# single_psg.net
KiCad netlist of a schematic drawn in EAGLE
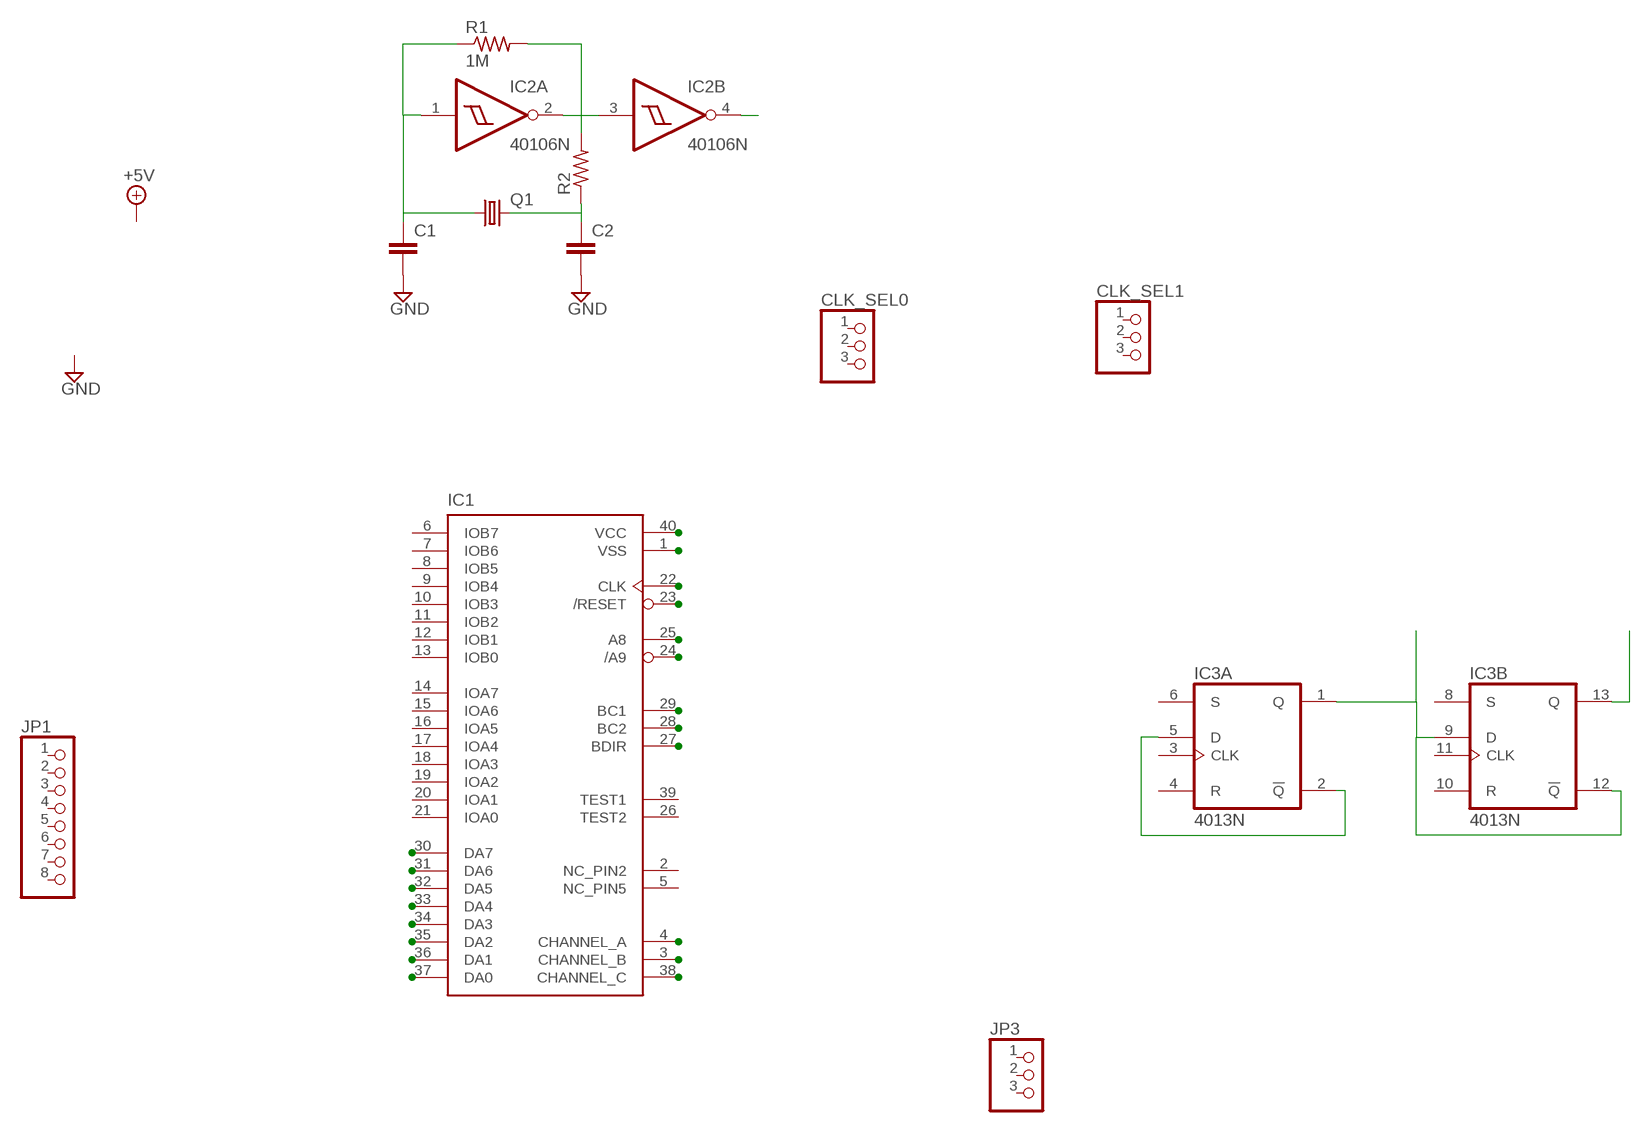
[diagram p0: schematic, sheet 1]

(export (version "E")
  (design (tool "Eeschema 10.0.6"))
  (components
    (comp (ref "C1")
      (value "050X030_0252")
      (footprint "eagle-import:050X030_025_2")
      (libsource (lib "eagle-import") (part "050X030_0252"))
    )
    (comp (ref "C2")
      (value "050X030_0252")
      (footprint "eagle-import:050X030_025_2")
      (libsource (lib "eagle-import") (part "050X030_0252"))
    )
    (comp (ref "CLK_SEL0")
      (value "PINHD-1X3")
      (footprint "eagle-import:1X03")
      (libsource (lib "eagle-import") (part "PINHD-1X3"))
    )
    (comp (ref "CLK_SEL1")
      (value "PINHD-1X3")
      (footprint "eagle-import:1X03")
      (libsource (lib "eagle-import") (part "PINHD-1X3"))
    )
    (comp (ref "IC1")
      (value "AY-3-8910")
      (footprint "eagle-import:DIL40")
      (libsource (lib "eagle-import") (part "AY-3-8910"))
    )
    (comp (ref "IC2")
      (value "40106N")
      (footprint "eagle-import:DIL14")
      (libsource (lib "eagle-import") (part "40106N"))
    )
    (comp (ref "IC3")
      (value "4013N")
      (footprint "eagle-import:DIL14")
      (libsource (lib "eagle-import") (part "4013N"))
    )
    (comp (ref "JP1")
      (value "PINHD-1X8")
      (footprint "eagle-import:1X08")
      (libsource (lib "eagle-import") (part "PINHD-1X8"))
    )
    (comp (ref "JP3")
      (value "PINHD-1X3")
      (footprint "eagle-import:1X03")
      (libsource (lib "eagle-import") (part "PINHD-1X3"))
    )
    (comp (ref "Q1")
      (value "CRYSTALHC18U-V")
      (footprint "eagle-import:HC18U-V")
      (libsource (lib "eagle-import") (part "CRYSTALHC18U-V"))
    )
    (comp (ref "R1")
      (value "1M")
      (footprint "eagle-import:R0207_3")
      (libsource (lib "eagle-import") (part "6MM.3"))
    )
    (comp (ref "R2")
      (value "6MM.3")
      (footprint "eagle-import:R0207_3")
      (libsource (lib "eagle-import") (part "6MM.3"))
    )
  )
  (nets
    (net (code "2") (name "/VCC") (class "Default")
      (node (ref "IC1") (pin "40") (pinfunction "VCC_40") (pintype "power_in"))
    )
    (net (code "3") (name "/VSS") (class "Default")
      (node (ref "IC1") (pin "1") (pinfunction "VSS_1") (pintype "power_in"))
    )
    (net (code "4") (name "GND") (class "Default")
      (node (ref "C1") (pin "2") (pinfunction "2_2") (pintype "passive"))
      (node (ref "C2") (pin "2") (pinfunction "2_2") (pintype "passive"))
    )
    (net (code "5") (name "Net-(C2-Pad1)") (class "Default")
      (node (ref "C2") (pin "1") (pinfunction "1_1") (pintype "passive"))
      (node (ref "Q1") (pin "2") (pinfunction "2_2") (pintype "passive"))
      (node (ref "R2") (pin "1") (pinfunction "1_1") (pintype "passive"))
    )
    (net (code "6") (name "Net-(IC2A-I)") (class "Default")
      (node (ref "C1") (pin "1") (pinfunction "1_1") (pintype "passive"))
      (node (ref "IC2") (pin "1") (pinfunction "I_1") (pintype "input"))
      (node (ref "Q1") (pin "1") (pinfunction "1_1") (pintype "passive"))
      (node (ref "R1") (pin "1") (pinfunction "1_1") (pintype "passive"))
    )
    (net (code "7") (name "Net-(IC2A-O)") (class "Default")
      (node (ref "IC2") (pin "2") (pinfunction "O_2") (pintype "output"))
      (node (ref "IC2") (pin "3") (pinfunction "I_3") (pintype "input"))
      (node (ref "R1") (pin "2") (pinfunction "2_2") (pintype "passive"))
      (node (ref "R2") (pin "2") (pinfunction "2_2") (pintype "passive"))
    )
    (net (code "8") (name "Net-(IC3A-D)") (class "Default")
      (node (ref "IC3") (pin "2") (pinfunction "~{Q}_2") (pintype "output"))
      (node (ref "IC3") (pin "5") (pinfunction "D_5") (pintype "input"))
    )
    (net (code "9") (name "Net-(IC3A-Q)") (class "Default")
      (node (ref "IC3") (pin "1") (pinfunction "Q_1") (pintype "output"))
      (node (ref "IC3") (pin "12") (pinfunction "~{Q}_12") (pintype "output"))
      (node (ref "IC3") (pin "9") (pinfunction "D_9") (pintype "input"))
    )
    (net (code "10") (name "unconnected-(CLK_SEL0-Pad1)") (class "Default")
      (node (ref "CLK_SEL0") (pin "1") (pinfunction "1_1") (pintype "passive"))
    )
    (net (code "11") (name "unconnected-(CLK_SEL0-Pad2)") (class "Default")
      (node (ref "CLK_SEL0") (pin "2") (pinfunction "2_2") (pintype "passive"))
    )
    (net (code "12") (name "unconnected-(CLK_SEL0-Pad3)") (class "Default")
      (node (ref "CLK_SEL0") (pin "3") (pinfunction "3_3") (pintype "passive"))
    )
    (net (code "13") (name "unconnected-(CLK_SEL1-Pad1)") (class "Default")
      (node (ref "CLK_SEL1") (pin "1") (pinfunction "1_1") (pintype "passive"))
    )
    (net (code "14") (name "unconnected-(CLK_SEL1-Pad2)") (class "Default")
      (node (ref "CLK_SEL1") (pin "2") (pinfunction "2_2") (pintype "passive"))
    )
    (net (code "15") (name "unconnected-(CLK_SEL1-Pad3)") (class "Default")
      (node (ref "CLK_SEL1") (pin "3") (pinfunction "3_3") (pintype "passive"))
    )
    (net (code "16") (name "unconnected-(IC1-A8-Pad25)") (class "Default")
      (node (ref "IC1") (pin "25") (pinfunction "A8_25") (pintype "bidirectional"))
    )
    (net (code "17") (name "unconnected-(IC1-BC1-Pad29)") (class "Default")
      (node (ref "IC1") (pin "29") (pinfunction "BC1_29") (pintype "input"))
    )
    (net (code "18") (name "unconnected-(IC1-BC2-Pad28)") (class "Default")
      (node (ref "IC1") (pin "28") (pinfunction "BC2_28") (pintype "input"))
    )
    (net (code "19") (name "unconnected-(IC1-BDIR-Pad27)") (class "Default")
      (node (ref "IC1") (pin "27") (pinfunction "BDIR_27") (pintype "input"))
    )
    (net (code "20") (name "unconnected-(IC1-CHANNEL_A-Pad4)") (class "Default")
      (node (ref "IC1") (pin "4") (pinfunction "CHANNEL_A_4") (pintype "output"))
    )
    (net (code "21") (name "unconnected-(IC1-CHANNEL_B-Pad3)") (class "Default")
      (node (ref "IC1") (pin "3") (pinfunction "CHANNEL_B_3") (pintype "output"))
    )
    (net (code "22") (name "unconnected-(IC1-CHANNEL_C-Pad38)") (class "Default")
      (node (ref "IC1") (pin "38") (pinfunction "CHANNEL_C_38") (pintype "output"))
    )
    (net (code "23") (name "unconnected-(IC1-CLK-Pad22)") (class "Default")
      (node (ref "IC1") (pin "22") (pinfunction "CLK_22") (pintype "input"))
    )
    (net (code "24") (name "unconnected-(IC1-DA0-Pad37)") (class "Default")
      (node (ref "IC1") (pin "37") (pinfunction "DA0_37") (pintype "bidirectional"))
    )
    (net (code "25") (name "unconnected-(IC1-DA1-Pad36)") (class "Default")
      (node (ref "IC1") (pin "36") (pinfunction "DA1_36") (pintype "bidirectional"))
    )
    (net (code "26") (name "unconnected-(IC1-DA2-Pad35)") (class "Default")
      (node (ref "IC1") (pin "35") (pinfunction "DA2_35") (pintype "bidirectional"))
    )
    (net (code "27") (name "unconnected-(IC1-DA3-Pad34)") (class "Default")
      (node (ref "IC1") (pin "34") (pinfunction "DA3_34") (pintype "bidirectional"))
    )
    (net (code "28") (name "unconnected-(IC1-DA4-Pad33)") (class "Default")
      (node (ref "IC1") (pin "33") (pinfunction "DA4_33") (pintype "bidirectional"))
    )
    (net (code "29") (name "unconnected-(IC1-DA5-Pad32)") (class "Default")
      (node (ref "IC1") (pin "32") (pinfunction "DA5_32") (pintype "bidirectional"))
    )
    (net (code "30") (name "unconnected-(IC1-DA6-Pad31)") (class "Default")
      (node (ref "IC1") (pin "31") (pinfunction "DA6_31") (pintype "bidirectional"))
    )
    (net (code "31") (name "unconnected-(IC1-DA7-Pad30)") (class "Default")
      (node (ref "IC1") (pin "30") (pinfunction "DA7_30") (pintype "bidirectional"))
    )
    (net (code "32") (name "unconnected-(IC1-IOA0-Pad21)") (class "Default")
      (node (ref "IC1") (pin "21") (pinfunction "IOA0_21") (pintype "bidirectional"))
    )
    (net (code "33") (name "unconnected-(IC1-IOA1-Pad20)") (class "Default")
      (node (ref "IC1") (pin "20") (pinfunction "IOA1_20") (pintype "bidirectional"))
    )
    (net (code "34") (name "unconnected-(IC1-IOA2-Pad19)") (class "Default")
      (node (ref "IC1") (pin "19") (pinfunction "IOA2_19") (pintype "bidirectional"))
    )
    (net (code "35") (name "unconnected-(IC1-IOA3-Pad18)") (class "Default")
      (node (ref "IC1") (pin "18") (pinfunction "IOA3_18") (pintype "bidirectional"))
    )
    (net (code "36") (name "unconnected-(IC1-IOA4-Pad17)") (class "Default")
      (node (ref "IC1") (pin "17") (pinfunction "IOA4_17") (pintype "bidirectional"))
    )
    (net (code "37") (name "unconnected-(IC1-IOA5-Pad16)") (class "Default")
      (node (ref "IC1") (pin "16") (pinfunction "IOA5_16") (pintype "bidirectional"))
    )
    (net (code "38") (name "unconnected-(IC1-IOA6-Pad15)") (class "Default")
      (node (ref "IC1") (pin "15") (pinfunction "IOA6_15") (pintype "bidirectional"))
    )
    (net (code "39") (name "unconnected-(IC1-IOA7-Pad14)") (class "Default")
      (node (ref "IC1") (pin "14") (pinfunction "IOA7_14") (pintype "bidirectional"))
    )
    (net (code "40") (name "unconnected-(IC1-IOB0-Pad13)") (class "Default")
      (node (ref "IC1") (pin "13") (pinfunction "IOB0_13") (pintype "bidirectional"))
    )
    (net (code "41") (name "unconnected-(IC1-IOB1-Pad12)") (class "Default")
      (node (ref "IC1") (pin "12") (pinfunction "IOB1_12") (pintype "bidirectional"))
    )
    (net (code "42") (name "unconnected-(IC1-IOB2-Pad11)") (class "Default")
      (node (ref "IC1") (pin "11") (pinfunction "IOB2_11") (pintype "bidirectional"))
    )
    (net (code "43") (name "unconnected-(IC1-IOB3-Pad10)") (class "Default")
      (node (ref "IC1") (pin "10") (pinfunction "IOB3_10") (pintype "bidirectional"))
    )
    (net (code "44") (name "unconnected-(IC1-IOB4-Pad9)") (class "Default")
      (node (ref "IC1") (pin "9") (pinfunction "IOB4_9") (pintype "bidirectional"))
    )
    (net (code "45") (name "unconnected-(IC1-IOB5-Pad8)") (class "Default")
      (node (ref "IC1") (pin "8") (pinfunction "IOB5_8") (pintype "bidirectional"))
    )
    (net (code "46") (name "unconnected-(IC1-IOB6-Pad7)") (class "Default")
      (node (ref "IC1") (pin "7") (pinfunction "IOB6_7") (pintype "bidirectional"))
    )
    (net (code "47") (name "unconnected-(IC1-IOB7-Pad6)") (class "Default")
      (node (ref "IC1") (pin "6") (pinfunction "IOB7_6") (pintype "bidirectional"))
    )
    (net (code "48") (name "unconnected-(IC1-NC_PIN2-Pad2)") (class "Default")
      (node (ref "IC1") (pin "2") (pinfunction "NC_PIN2_2") (pintype "no_connect"))
    )
    (net (code "49") (name "unconnected-(IC1-NC_PIN5-Pad5)") (class "Default")
      (node (ref "IC1") (pin "5") (pinfunction "NC_PIN5_5") (pintype "bidirectional"))
    )
    (net (code "50") (name "unconnected-(IC1-TEST1-Pad39)") (class "Default")
      (node (ref "IC1") (pin "39") (pinfunction "TEST1_39") (pintype "no_connect"))
    )
    (net (code "51") (name "unconnected-(IC1-TEST2-Pad26)") (class "Default")
      (node (ref "IC1") (pin "26") (pinfunction "TEST2_26") (pintype "no_connect"))
    )
    (net (code "52") (name "unconnected-(IC1-{slash}A9-Pad24)") (class "Default")
      (node (ref "IC1") (pin "24") (pinfunction "/A9_24") (pintype "bidirectional"))
    )
    (net (code "53") (name "unconnected-(IC1-{slash}RESET-Pad23)") (class "Default")
      (node (ref "IC1") (pin "23") (pinfunction "/RESET_23") (pintype "input"))
    )
    (net (code "54") (name "unconnected-(IC2B-O-Pad4)") (class "Default")
      (node (ref "IC2") (pin "4") (pinfunction "O_4") (pintype "output"))
    )
    (net (code "55") (name "unconnected-(IC3A-CLK-Pad3)") (class "Default")
      (node (ref "IC3") (pin "3") (pinfunction "CLK_3") (pintype "input"))
    )
    (net (code "56") (name "unconnected-(IC3A-R-Pad4)") (class "Default")
      (node (ref "IC3") (pin "4") (pinfunction "R_4") (pintype "input"))
    )
    (net (code "57") (name "unconnected-(IC3A-S-Pad6)") (class "Default")
      (node (ref "IC3") (pin "6") (pinfunction "S_6") (pintype "input"))
    )
    (net (code "58") (name "unconnected-(IC3B-CLK-Pad11)") (class "Default")
      (node (ref "IC3") (pin "11") (pinfunction "CLK_11") (pintype "input"))
    )
    (net (code "59") (name "unconnected-(IC3B-Q-Pad13)") (class "Default")
      (node (ref "IC3") (pin "13") (pinfunction "Q_13") (pintype "output"))
    )
    (net (code "60") (name "unconnected-(IC3B-R-Pad10)") (class "Default")
      (node (ref "IC3") (pin "10") (pinfunction "R_10") (pintype "input"))
    )
    (net (code "61") (name "unconnected-(IC3B-S-Pad8)") (class "Default")
      (node (ref "IC3") (pin "8") (pinfunction "S_8") (pintype "input"))
    )
    (net (code "62") (name "unconnected-(JP1-Pad1)") (class "Default")
      (node (ref "JP1") (pin "1") (pinfunction "1_1") (pintype "passive"))
    )
    (net (code "63") (name "unconnected-(JP1-Pad2)") (class "Default")
      (node (ref "JP1") (pin "2") (pinfunction "2_2") (pintype "passive"))
    )
    (net (code "64") (name "unconnected-(JP1-Pad3)") (class "Default")
      (node (ref "JP1") (pin "3") (pinfunction "3_3") (pintype "passive"))
    )
    (net (code "65") (name "unconnected-(JP1-Pad4)") (class "Default")
      (node (ref "JP1") (pin "4") (pinfunction "4_4") (pintype "passive"))
    )
    (net (code "66") (name "unconnected-(JP1-Pad5)") (class "Default")
      (node (ref "JP1") (pin "5") (pinfunction "5_5") (pintype "passive"))
    )
    (net (code "67") (name "unconnected-(JP1-Pad6)") (class "Default")
      (node (ref "JP1") (pin "6") (pinfunction "6_6") (pintype "passive"))
    )
    (net (code "68") (name "unconnected-(JP1-Pad7)") (class "Default")
      (node (ref "JP1") (pin "7") (pinfunction "7_7") (pintype "passive"))
    )
    (net (code "69") (name "unconnected-(JP1-Pad8)") (class "Default")
      (node (ref "JP1") (pin "8") (pinfunction "8_8") (pintype "passive"))
    )
    (net (code "70") (name "unconnected-(JP3-Pad1)") (class "Default")
      (node (ref "JP3") (pin "1") (pinfunction "1_1") (pintype "passive"))
    )
    (net (code "71") (name "unconnected-(JP3-Pad2)") (class "Default")
      (node (ref "JP3") (pin "2") (pinfunction "2_2") (pintype "passive"))
    )
    (net (code "72") (name "unconnected-(JP3-Pad3)") (class "Default")
      (node (ref "JP3") (pin "3") (pinfunction "3_3") (pintype "passive"))
    )
  )
)
